# TheSiS.net
KiCad netlist of a schematic drawn in EAGLE
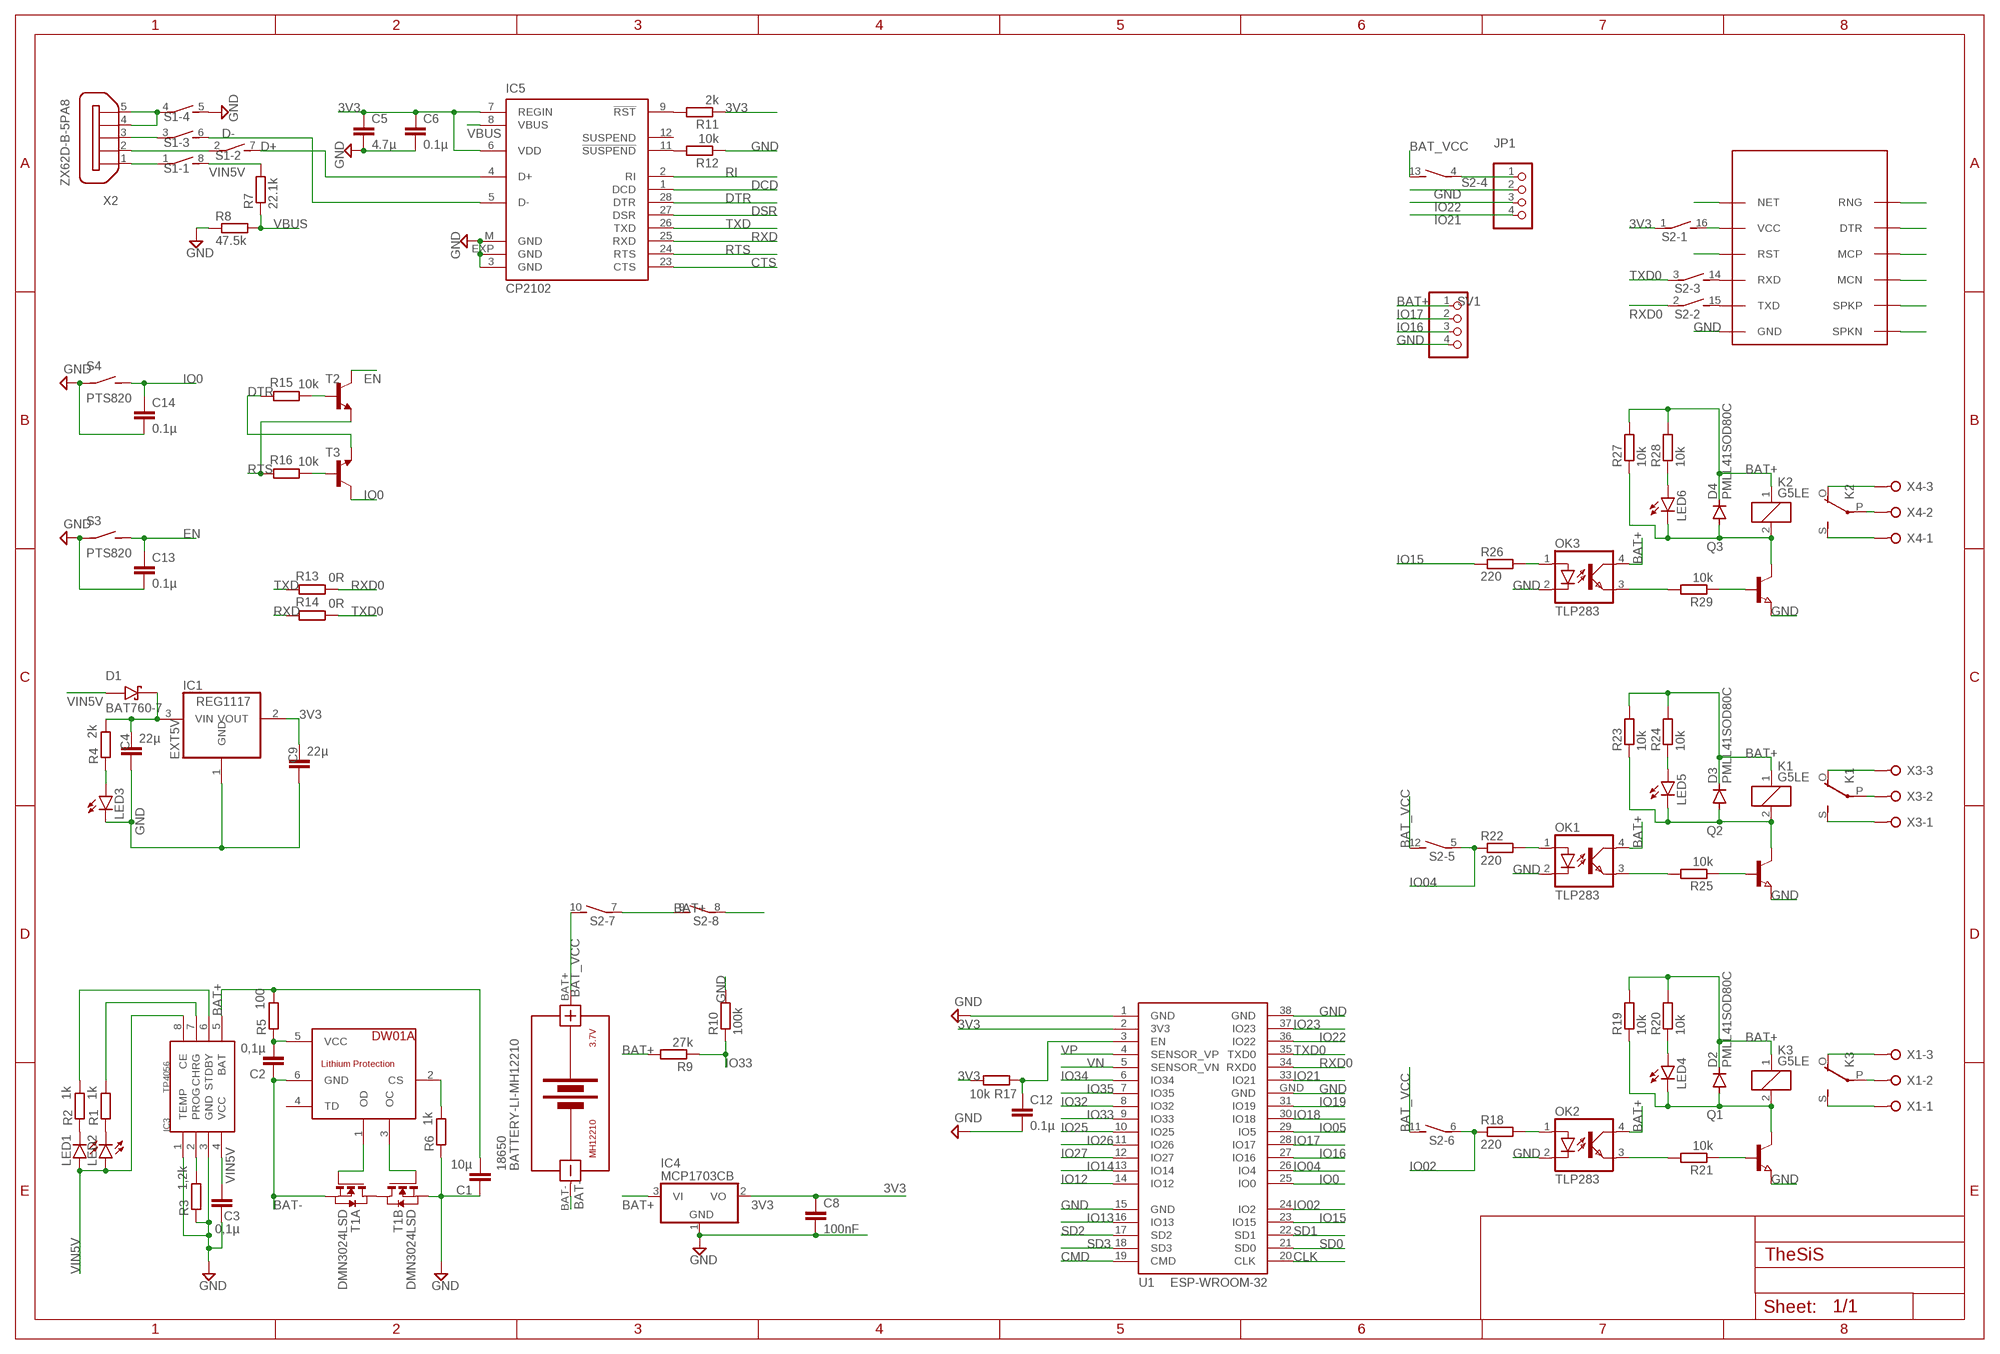
[diagram p0: schematic, sheet 1]

(export (version "E")
  (design (tool "Eeschema 10.0.6"))
  (components
    (comp (ref "18650")
      (value "BATTERY-LI-MH12210")
      (footprint "eagle-import:BATTERY-LI-MH12210")
      (libsource (lib "eagle-import") (part "BATTERY-LI-MH12210"))
    )
    (comp (ref "C1")
      (value "10µ")
      (footprint "eagle-import:C0603")
      (libsource (lib "eagle-import") (part "C-EUC0603"))
    )
    (comp (ref "C2")
      (value "0,1µ")
      (footprint "eagle-import:C0805")
      (libsource (lib "eagle-import") (part "C-EUC0805"))
    )
    (comp (ref "C3")
      (value "0,1µ")
      (footprint "eagle-import:C0805K")
      (libsource (lib "eagle-import") (part "C-EUC0805K"))
    )
    (comp (ref "C4")
      (value "22µ")
      (footprint "eagle-import:C0805")
      (libsource (lib "eagle-import") (part "C-EUC0805"))
    )
    (comp (ref "C5")
      (value "4.7µ")
      (footprint "eagle-import:C0805")
      (libsource (lib "eagle-import") (part "C-EUC0805"))
    )
    (comp (ref "C6")
      (value "0.1µ")
      (footprint "eagle-import:C0805")
      (libsource (lib "eagle-import") (part "C-EUC0805"))
    )
    (comp (ref "C8")
      (value "100nF")
      (footprint "eagle-import:C0805")
      (libsource (lib "eagle-import") (part "C-EUC0805"))
    )
    (comp (ref "C9")
      (value "22µ")
      (footprint "eagle-import:C0805")
      (libsource (lib "eagle-import") (part "C-EUC0805"))
    )
    (comp (ref "C12")
      (value "0.1µ")
      (footprint "eagle-import:C0805")
      (libsource (lib "eagle-import") (part "C-EUC0805"))
    )
    (comp (ref "C13")
      (value "0.1µ")
      (footprint "eagle-import:C0805")
      (libsource (lib "eagle-import") (part "C-EUC0805"))
    )
    (comp (ref "C14")
      (value "0.1µ")
      (footprint "eagle-import:C0805")
      (libsource (lib "eagle-import") (part "C-EUC0805"))
    )
    (comp (ref "D1")
      (value "BAT760-7")
      (footprint "eagle-import:SOD2513X120N")
      (fields (field (name "MF") "Diodes Inc."))
      (libsource (lib "eagle-import") (part "BAT760-7"))
    )
    (comp (ref "D2")
      (value "PMLL41SOD80C")
      (footprint "eagle-import:SOD80C")
      (libsource (lib "eagle-import") (part "PMLL41SOD80C"))
    )
    (comp (ref "D3")
      (value "PMLL41SOD80C")
      (footprint "eagle-import:SOD80C")
      (libsource (lib "eagle-import") (part "PMLL41SOD80C"))
    )
    (comp (ref "D4")
      (value "PMLL41SOD80C")
      (footprint "eagle-import:SOD80C")
      (libsource (lib "eagle-import") (part "PMLL41SOD80C"))
    )
    (comp (ref "IC1")
      (value "REG1117")
      (footprint "eagle-import:SOT223A")
      (libsource (lib "eagle-import") (part "REG1117"))
    )
    (comp (ref "IC3")
      (value "TP4056")
      (footprint "eagle-import:SOP-8")
      (libsource (lib "eagle-import") (part "TP4056"))
    )
    (comp (ref "IC4")
      (value "MCP1703CB")
      (footprint "eagle-import:SOT23")
      (libsource (lib "eagle-import") (part "MCP1703CB"))
    )
    (comp (ref "IC5")
      (value "CP2102")
      (footprint "eagle-import:QFN28")
      (fields (field (name "MF") "FARNELL") (field (name "MPN") "CP2102-GM"))
      (libsource (lib "eagle-import") (part "CP2102"))
    )
    (comp (ref "JP1")
      (value "PINHD-1X4")
      (footprint "eagle-import:1X04")
      (libsource (lib "eagle-import") (part "PINHD-1X4"))
    )
    (comp (ref "K1")
      (value "G5LE")
      (footprint "eagle-import:G5LE")
      (libsource (lib "eagle-import") (part "G5LE"))
    )
    (comp (ref "K2")
      (value "G5LE")
      (footprint "eagle-import:G5LE")
      (libsource (lib "eagle-import") (part "G5LE"))
    )
    (comp (ref "K3")
      (value "G5LE")
      (footprint "eagle-import:G5LE")
      (libsource (lib "eagle-import") (part "G5LE"))
    )
    (comp (ref "LED1")
      (value "LEDCHIP-LED0805")
      (footprint "eagle-import:CHIP-LED0805")
      (libsource (lib "eagle-import") (part "LEDCHIP-LED0805"))
    )
    (comp (ref "LED2")
      (value "LEDCHIP-LED0805")
      (footprint "eagle-import:CHIP-LED0805")
      (libsource (lib "eagle-import") (part "LEDCHIP-LED0805"))
    )
    (comp (ref "LED3")
      (value "LEDCHIP-LED0805")
      (footprint "eagle-import:CHIP-LED0805")
      (libsource (lib "eagle-import") (part "LEDCHIP-LED0805"))
    )
    (comp (ref "LED4")
      (value "LEDCHIP-LED0805")
      (footprint "eagle-import:CHIP-LED0805")
      (libsource (lib "eagle-import") (part "LEDCHIP-LED0805"))
    )
    (comp (ref "LED5")
      (value "LEDCHIP-LED0805")
      (footprint "eagle-import:CHIP-LED0805")
      (libsource (lib "eagle-import") (part "LEDCHIP-LED0805"))
    )
    (comp (ref "LED6")
      (value "LEDCHIP-LED0805")
      (footprint "eagle-import:CHIP-LED0805")
      (libsource (lib "eagle-import") (part "LEDCHIP-LED0805"))
    )
    (comp (ref "OK1")
      (value "TLP283")
      (footprint "eagle-import:SOT23-4")
      (libsource (lib "eagle-import") (part "TLP283"))
    )
    (comp (ref "OK2")
      (value "TLP283")
      (footprint "eagle-import:SOT23-4")
      (libsource (lib "eagle-import") (part "TLP283"))
    )
    (comp (ref "OK3")
      (value "TLP283")
      (footprint "eagle-import:SOT23-4")
      (libsource (lib "eagle-import") (part "TLP283"))
    )
    (comp (ref "Q1")
      (value "NPN-TRANSISTOR_SOT23")
      (footprint "eagle-import:SOT23")
      (libsource (lib "eagle-import") (part "NPN-TRANSISTOR_SOT23"))
    )
    (comp (ref "Q2")
      (value "NPN-TRANSISTOR_SOT23")
      (footprint "eagle-import:SOT23")
      (libsource (lib "eagle-import") (part "NPN-TRANSISTOR_SOT23"))
    )
    (comp (ref "Q3")
      (value "NPN-TRANSISTOR_SOT23")
      (footprint "eagle-import:SOT23")
      (libsource (lib "eagle-import") (part "NPN-TRANSISTOR_SOT23"))
    )
    (comp (ref "R1")
      (value "1k")
      (footprint "eagle-import:R0603")
      (libsource (lib "eagle-import") (part "R-EU_R0603"))
    )
    (comp (ref "R2")
      (value "1k")
      (footprint "eagle-import:R0603")
      (libsource (lib "eagle-import") (part "R-EU_R0603"))
    )
    (comp (ref "R3")
      (value "1,2k")
      (footprint "eagle-import:R0603")
      (libsource (lib "eagle-import") (part "R-EU_R0603"))
    )
    (comp (ref "R4")
      (value "2k")
      (footprint "eagle-import:R0805")
      (libsource (lib "eagle-import") (part "R-EU_R0805"))
    )
    (comp (ref "R5")
      (value "100")
      (footprint "eagle-import:R0603")
      (libsource (lib "eagle-import") (part "R-EU_R0603"))
    )
    (comp (ref "R6")
      (value "1k")
      (footprint "eagle-import:R0603")
      (libsource (lib "eagle-import") (part "R-EU_R0603"))
    )
    (comp (ref "R7")
      (value "22.1k")
      (footprint "eagle-import:R0805")
      (libsource (lib "eagle-import") (part "R-EU_R0805"))
    )
    (comp (ref "R8")
      (value "47.5k")
      (footprint "eagle-import:R0805")
      (libsource (lib "eagle-import") (part "R-EU_R0805"))
    )
    (comp (ref "R9")
      (value "27k")
      (footprint "eagle-import:R0805")
      (libsource (lib "eagle-import") (part "R-EU_R0805"))
    )
    (comp (ref "R10")
      (value "100k")
      (footprint "eagle-import:R0805")
      (libsource (lib "eagle-import") (part "R-EU_R0805"))
    )
    (comp (ref "R11")
      (value "2k")
      (footprint "eagle-import:R0805")
      (libsource (lib "eagle-import") (part "R-EU_R0805"))
    )
    (comp (ref "R12")
      (value "10k")
      (footprint "eagle-import:R0805")
      (libsource (lib "eagle-import") (part "R-EU_R0805"))
    )
    (comp (ref "R13")
      (value "0R")
      (footprint "eagle-import:R0805")
      (libsource (lib "eagle-import") (part "R-EU_R0805"))
    )
    (comp (ref "R14")
      (value "0R")
      (footprint "eagle-import:R0805")
      (libsource (lib "eagle-import") (part "R-EU_R0805"))
    )
    (comp (ref "R15")
      (value "10k")
      (footprint "eagle-import:R0805")
      (libsource (lib "eagle-import") (part "R-EU_R0805"))
    )
    (comp (ref "R16")
      (value "10k")
      (footprint "eagle-import:R0805")
      (libsource (lib "eagle-import") (part "R-EU_R0805"))
    )
    (comp (ref "R17")
      (value "10k")
      (footprint "eagle-import:R0805")
      (libsource (lib "eagle-import") (part "R-EU_R0805"))
    )
    (comp (ref "R18")
      (value "220")
      (footprint "eagle-import:R0805")
      (libsource (lib "eagle-import") (part "R-EU_R0805"))
    )
    (comp (ref "R19")
      (value "10k")
      (footprint "eagle-import:R0805")
      (libsource (lib "eagle-import") (part "R-EU_R0805"))
    )
    (comp (ref "R20")
      (value "10k")
      (footprint "eagle-import:R0805")
      (libsource (lib "eagle-import") (part "R-EU_R0805"))
    )
    (comp (ref "R21")
      (value "10k")
      (footprint "eagle-import:R0805")
      (libsource (lib "eagle-import") (part "R-EU_R0805"))
    )
    (comp (ref "R22")
      (value "220")
      (footprint "eagle-import:R0805")
      (libsource (lib "eagle-import") (part "R-EU_R0805"))
    )
    (comp (ref "R23")
      (value "10k")
      (footprint "eagle-import:R0805")
      (libsource (lib "eagle-import") (part "R-EU_R0805"))
    )
    (comp (ref "R24")
      (value "10k")
      (footprint "eagle-import:R0805")
      (libsource (lib "eagle-import") (part "R-EU_R0805"))
    )
    (comp (ref "R25")
      (value "10k")
      (footprint "eagle-import:R0805")
      (libsource (lib "eagle-import") (part "R-EU_R0805"))
    )
    (comp (ref "R26")
      (value "220")
      (footprint "eagle-import:R0805")
      (libsource (lib "eagle-import") (part "R-EU_R0805"))
    )
    (comp (ref "R27")
      (value "10k")
      (footprint "eagle-import:R0805")
      (libsource (lib "eagle-import") (part "R-EU_R0805"))
    )
    (comp (ref "R28")
      (value "10k")
      (footprint "eagle-import:R0805")
      (libsource (lib "eagle-import") (part "R-EU_R0805"))
    )
    (comp (ref "R29")
      (value "10k")
      (footprint "eagle-import:R0805")
      (libsource (lib "eagle-import") (part "R-EU_R0805"))
    )
    (comp (ref "S1")
      (value "DIP04S")
      (footprint "eagle-import:DIP04S")
      (libsource (lib "eagle-import") (part "DIP04S"))
    )
    (comp (ref "S2")
      (value "DIP08S")
      (footprint "eagle-import:DIP08S")
      (libsource (lib "eagle-import") (part "DIP08S"))
    )
    (comp (ref "S3")
      (value "PTS820")
      (footprint "eagle-import:PTS820")
      (libsource (lib "eagle-import") (part "PTS820"))
    )
    (comp (ref "S4")
      (value "PTS820")
      (footprint "eagle-import:PTS820")
      (libsource (lib "eagle-import") (part "PTS820"))
    )
    (comp (ref "SV1")
      (value "PINHD-1X4")
      (footprint "eagle-import:1X04")
      (libsource (lib "eagle-import") (part "PINHD-1X4"))
    )
    (comp (ref "T1")
      (value "DMN3024LSD")
      (footprint "eagle-import:TSSOP-8")
      (libsource (lib "eagle-import") (part "DMN3024LSD"))
    )
    (comp (ref "T2")
      (value "-NPN-SOT23-EBC")
      (footprint "eagle-import:SOT23-EBC")
      (fields (field (name "SPICEPREFIX") "J"))
      (libsource (lib "eagle-import") (part "-NPN-SOT23-EBC"))
    )
    (comp (ref "T3")
      (value "-NPN-SOT23-EBC")
      (footprint "eagle-import:SOT23-EBC")
      (fields (field (name "SPICEPREFIX") "J"))
      (libsource (lib "eagle-import") (part "-NPN-SOT23-EBC"))
    )
    (comp (ref "U$1")
      (value "DW01A")
      (footprint "eagle-import:SOT23-6")
      (libsource (lib "eagle-import") (part "DW01A"))
    )
    (comp (ref "U$4")
      (value "SIM800L")
      (footprint "eagle-import:SIM-CORE")
      (libsource (lib "eagle-import") (part "SIM800L"))
    )
    (comp (ref "U1")
      (value "ESP-WROOM-32")
      (footprint "eagle-import:ESP-WROOM-32")
      (libsource (lib "eagle-import") (part "ESP-WROOM-32"))
    )
    (comp (ref "X1")
      (value "W237-03P")
      (footprint "eagle-import:W237-3")
      (libsource (lib "eagle-import") (part "W237-03P"))
    )
    (comp (ref "X2")
      (value "ZX62D-B-5PA8")
      (footprint "eagle-import:ZX62D-B-5PA8")
      (fields (field (name "MF") "Hirose"))
      (libsource (lib "eagle-import") (part "ZX62D-B-5PA8"))
    )
    (comp (ref "X3")
      (value "W237-03P")
      (footprint "eagle-import:W237-3")
      (libsource (lib "eagle-import") (part "W237-03P"))
    )
    (comp (ref "X4")
      (value "W237-03P")
      (footprint "eagle-import:W237-3")
      (libsource (lib "eagle-import") (part "W237-03P"))
    )
  )
  (nets
    (net (code "1") (name "/3V3") (class "Default")
      (node (ref "C5") (pin "1") (pinfunction "1_1") (pintype "passive"))
      (node (ref "C6") (pin "1") (pinfunction "1_1") (pintype "passive"))
      (node (ref "C8") (pin "1") (pinfunction "1_1") (pintype "passive"))
      (node (ref "C9") (pin "1") (pinfunction "1_1") (pintype "passive"))
      (node (ref "IC1") (pin "2") (pinfunction "VOUT_2") (pintype "output"))
      (node (ref "IC4") (pin "2") (pinfunction "VO_2") (pintype "passive"))
      (node (ref "IC5") (pin "6") (pinfunction "VDD_6") (pintype "power_in"))
      (node (ref "IC5") (pin "7") (pinfunction "REGIN_7") (pintype "passive"))
      (node (ref "R11") (pin "1") (pinfunction "1_1") (pintype "passive"))
      (node (ref "R17") (pin "2") (pinfunction "2_2") (pintype "passive"))
      (node (ref "S2") (pin "1") (pinfunction "1_1") (pintype "passive"))
      (node (ref "U1") (pin "2") (pinfunction "3V3_2") (pintype "power_in"))
    )
    (net (code "2") (name "/BAT+") (class "Default")
      (node (ref "C1") (pin "2") (pinfunction "2_2") (pintype "passive"))
      (node (ref "D2") (pin "C") (pinfunction "C_C") (pintype "passive"))
      (node (ref "D3") (pin "C") (pinfunction "C_C") (pintype "passive"))
      (node (ref "D4") (pin "C") (pinfunction "C_C") (pintype "passive"))
      (node (ref "IC3") (pin "5") (pinfunction "BAT_5") (pintype "bidirectional"))
      (node (ref "IC4") (pin "3") (pinfunction "VI_3") (pintype "input"))
      (node (ref "K1") (pin "1") (pinfunction "1_1") (pintype "passive"))
      (node (ref "K2") (pin "1") (pinfunction "1_1") (pintype "passive"))
      (node (ref "K3") (pin "1") (pinfunction "1_1") (pintype "passive"))
      (node (ref "OK1") (pin "4") (pinfunction "COL_4") (pintype "passive"))
      (node (ref "OK2") (pin "4") (pinfunction "COL_4") (pintype "passive"))
      (node (ref "OK3") (pin "4") (pinfunction "COL_4") (pintype "passive"))
      (node (ref "R19") (pin "2") (pinfunction "2_2") (pintype "passive"))
      (node (ref "R20") (pin "2") (pinfunction "2_2") (pintype "passive"))
      (node (ref "R23") (pin "2") (pinfunction "2_2") (pintype "passive"))
      (node (ref "R24") (pin "2") (pinfunction "2_2") (pintype "passive"))
      (node (ref "R27") (pin "2") (pinfunction "2_2") (pintype "passive"))
      (node (ref "R28") (pin "2") (pinfunction "2_2") (pintype "passive"))
      (node (ref "R5") (pin "2") (pinfunction "2_2") (pintype "passive"))
      (node (ref "R9") (pin "2") (pinfunction "2_2") (pintype "passive"))
      (node (ref "S2") (pin "8") (pinfunction "1_8") (pintype "passive"))
      (node (ref "SV1") (pin "1") (pinfunction "1_1") (pintype "passive"))
    )
    (net (code "3") (name "/BAT-") (class "Default")
      (node (ref "18650") (pin "BAT-") (pinfunction "BAT-_BAT-") (pintype "power_in"))
      (node (ref "C2") (pin "1") (pinfunction "1_1") (pintype "passive"))
      (node (ref "T1") (pin "2") (pinfunction "S_2") (pintype "passive"))
      (node (ref "T1") (pin "3") (pinfunction "S_3") (pintype "passive"))
      (node (ref "U$1") (pin "6") (pinfunction "GND_6") (pintype "bidirectional"))
    )
    (net (code "4") (name "/BAT_VCC") (class "Default")
      (node (ref "18650") (pin "BAT+") (pinfunction "BAT+_BAT+") (pintype "power_in"))
      (node (ref "S2") (pin "10") (pinfunction "2_10") (pintype "passive"))
      (node (ref "S2") (pin "11") (pinfunction "2_11") (pintype "passive"))
      (node (ref "S2") (pin "12") (pinfunction "2_12") (pintype "passive"))
      (node (ref "S2") (pin "13") (pinfunction "2_13") (pintype "passive"))
    )
    (net (code "5") (name "/CLK") (class "Default")
      (node (ref "U1") (pin "20") (pinfunction "CLK_20") (pintype "bidirectional"))
    )
    (net (code "6") (name "/CMD") (class "Default")
      (node (ref "U1") (pin "19") (pinfunction "CMD_19") (pintype "bidirectional"))
    )
    (net (code "7") (name "/CTS") (class "Default")
      (node (ref "IC5") (pin "23") (pinfunction "CTS_23") (pintype "input"))
    )
    (net (code "8") (name "/D+") (class "Default")
      (node (ref "IC5") (pin "4") (pinfunction "D+_4") (pintype "bidirectional"))
      (node (ref "S1") (pin "7") (pinfunction "2_7") (pintype "passive"))
    )
    (net (code "9") (name "/D-") (class "Default")
      (node (ref "IC5") (pin "5") (pinfunction "D-_5") (pintype "bidirectional"))
      (node (ref "S1") (pin "6") (pinfunction "2_6") (pintype "passive"))
    )
    (net (code "10") (name "/DCD") (class "Default")
      (node (ref "IC5") (pin "1") (pinfunction "DCD_1") (pintype "input"))
    )
    (net (code "11") (name "/DSR") (class "Default")
      (node (ref "IC5") (pin "27") (pinfunction "DSR_27") (pintype "input"))
    )
    (net (code "12") (name "/DTR") (class "Default")
      (node (ref "IC5") (pin "28") (pinfunction "DTR_28") (pintype "output"))
      (node (ref "R15") (pin "2") (pinfunction "2_2") (pintype "passive"))
      (node (ref "T3") (pin "E") (pinfunction "E_E") (pintype "passive"))
    )
    (net (code "13") (name "/EN") (class "Default")
      (node (ref "C13") (pin "1") (pinfunction "1_1") (pintype "passive"))
      (node (ref "S3") (pin "2") (pinfunction "S_2") (pintype "passive"))
      (node (ref "T2") (pin "C") (pinfunction "C_C") (pintype "passive"))
    )
    (net (code "14") (name "/EXT5V") (class "Default")
      (node (ref "C4") (pin "1") (pinfunction "1_1") (pintype "passive"))
      (node (ref "D1") (pin "C") (pinfunction "K_C") (pintype "passive"))
      (node (ref "IC1") (pin "3") (pinfunction "VIN_3") (pintype "input"))
      (node (ref "R4") (pin "2") (pinfunction "2_2") (pintype "passive"))
    )
    (net (code "15") (name "/IO0") (class "Default")
      (node (ref "C14") (pin "1") (pinfunction "1_1") (pintype "passive"))
      (node (ref "S4") (pin "2") (pinfunction "S_2") (pintype "passive"))
      (node (ref "T3") (pin "C") (pinfunction "C_C") (pintype "passive"))
      (node (ref "U1") (pin "25") (pinfunction "IO0_25") (pintype "bidirectional"))
    )
    (net (code "16") (name "/IO02") (class "Default")
      (node (ref "R18") (pin "1") (pinfunction "1_1") (pintype "passive"))
      (node (ref "S2") (pin "6") (pinfunction "1_6") (pintype "passive"))
      (node (ref "U1") (pin "24") (pinfunction "IO2_24") (pintype "bidirectional"))
    )
    (net (code "17") (name "/IO04") (class "Default")
      (node (ref "R22") (pin "1") (pinfunction "1_1") (pintype "passive"))
      (node (ref "S2") (pin "5") (pinfunction "1_5") (pintype "passive"))
      (node (ref "U1") (pin "26") (pinfunction "IO4_26") (pintype "bidirectional"))
    )
    (net (code "18") (name "/IO05") (class "Default")
      (node (ref "U1") (pin "29") (pinfunction "IO5_29") (pintype "bidirectional"))
    )
    (net (code "19") (name "/IO12") (class "Default")
      (node (ref "U1") (pin "14") (pinfunction "IO12_14") (pintype "bidirectional"))
    )
    (net (code "20") (name "/IO13") (class "Default")
      (node (ref "U1") (pin "16") (pinfunction "IO13_16") (pintype "bidirectional"))
    )
    (net (code "21") (name "/IO14") (class "Default")
      (node (ref "U1") (pin "13") (pinfunction "IO14_13") (pintype "bidirectional"))
    )
    (net (code "22") (name "/IO15") (class "Default")
      (node (ref "R26") (pin "1") (pinfunction "1_1") (pintype "passive"))
      (node (ref "U1") (pin "23") (pinfunction "IO15_23") (pintype "bidirectional"))
    )
    (net (code "23") (name "/IO16") (class "Default")
      (node (ref "SV1") (pin "3") (pinfunction "3_3") (pintype "passive"))
      (node (ref "U1") (pin "27") (pinfunction "IO16_27") (pintype "bidirectional"))
    )
    (net (code "24") (name "/IO17") (class "Default")
      (node (ref "SV1") (pin "2") (pinfunction "2_2") (pintype "passive"))
      (node (ref "U1") (pin "28") (pinfunction "IO17_28") (pintype "bidirectional"))
    )
    (net (code "25") (name "/IO18") (class "Default")
      (node (ref "U1") (pin "30") (pinfunction "IO18_30") (pintype "bidirectional"))
    )
    (net (code "26") (name "/IO19") (class "Default")
      (node (ref "U1") (pin "31") (pinfunction "IO19_31") (pintype "bidirectional"))
    )
    (net (code "27") (name "/IO21") (class "Default")
      (node (ref "JP1") (pin "4") (pinfunction "4_4") (pintype "passive"))
      (node (ref "U1") (pin "33") (pinfunction "IO21_33") (pintype "bidirectional"))
    )
    (net (code "28") (name "/IO22") (class "Default")
      (node (ref "JP1") (pin "3") (pinfunction "3_3") (pintype "passive"))
      (node (ref "U1") (pin "36") (pinfunction "IO22_36") (pintype "bidirectional"))
    )
    (net (code "29") (name "/IO23") (class "Default")
      (node (ref "U1") (pin "37") (pinfunction "IO23_37") (pintype "bidirectional"))
    )
    (net (code "30") (name "/IO25") (class "Default")
      (node (ref "U1") (pin "10") (pinfunction "IO25_10") (pintype "bidirectional"))
    )
    (net (code "31") (name "/IO26") (class "Default")
      (node (ref "U1") (pin "11") (pinfunction "IO26_11") (pintype "bidirectional"))
    )
    (net (code "32") (name "/IO27") (class "Default")
      (node (ref "U1") (pin "12") (pinfunction "IO27_12") (pintype "bidirectional"))
    )
    (net (code "33") (name "/IO32") (class "Default")
      (node (ref "U1") (pin "8") (pinfunction "IO32_8") (pintype "bidirectional"))
    )
    (net (code "34") (name "/IO33") (class "Default")
      (node (ref "R10") (pin "1") (pinfunction "1_1") (pintype "passive"))
      (node (ref "R9") (pin "1") (pinfunction "1_1") (pintype "passive"))
      (node (ref "U1") (pin "9") (pinfunction "IO33_9") (pintype "bidirectional"))
    )
    (net (code "35") (name "/IO34") (class "Default")
      (node (ref "U1") (pin "6") (pinfunction "IO34_6") (pintype "bidirectional"))
    )
    (net (code "36") (name "/IO35") (class "Default")
      (node (ref "U1") (pin "7") (pinfunction "IO35_7") (pintype "bidirectional"))
    )
    (net (code "37") (name "/RI") (class "Default")
      (node (ref "IC5") (pin "2") (pinfunction "RI_2") (pintype "input"))
    )
    (net (code "38") (name "/RTS") (class "Default")
      (node (ref "IC5") (pin "24") (pinfunction "RTS_24") (pintype "output"))
      (node (ref "R16") (pin "2") (pinfunction "2_2") (pintype "passive"))
      (node (ref "T2") (pin "E") (pinfunction "E_E") (pintype "passive"))
    )
    (net (code "39") (name "/RXD") (class "Default")
      (node (ref "IC5") (pin "25") (pinfunction "RXD_25") (pintype "input"))
      (node (ref "R14") (pin "2") (pinfunction "2_2") (pintype "passive"))
    )
    (net (code "40") (name "/RXD0") (class "Default")
      (node (ref "R13") (pin "1") (pinfunction "1_1") (pintype "passive"))
      (node (ref "S2") (pin "2") (pinfunction "1_2") (pintype "passive"))
      (node (ref "U1") (pin "34") (pinfunction "RXD0_34") (pintype "bidirectional"))
    )
    (net (code "41") (name "/SD0") (class "Default")
      (node (ref "U1") (pin "21") (pinfunction "SD0_21") (pintype "bidirectional"))
    )
    (net (code "42") (name "/SD1") (class "Default")
      (node (ref "U1") (pin "22") (pinfunction "SD1_22") (pintype "bidirectional"))
    )
    (net (code "43") (name "/SD2") (class "Default")
      (node (ref "U1") (pin "17") (pinfunction "SD2_17") (pintype "bidirectional"))
    )
    (net (code "44") (name "/SD3") (class "Default")
      (node (ref "U1") (pin "18") (pinfunction "SD3_18") (pintype "bidirectional"))
    )
    (net (code "45") (name "/TXD") (class "Default")
      (node (ref "IC5") (pin "26") (pinfunction "TXD_26") (pintype "output"))
      (node (ref "R13") (pin "2") (pinfunction "2_2") (pintype "passive"))
    )
    (net (code "46") (name "/TXD0") (class "Default")
      (node (ref "R14") (pin "1") (pinfunction "1_1") (pintype "passive"))
      (node (ref "S2") (pin "3") (pinfunction "1_3") (pintype "passive"))
      (node (ref "U1") (pin "35") (pinfunction "TXD0_35") (pintype "bidirectional"))
    )
    (net (code "47") (name "/VBUS") (class "Default")
      (node (ref "IC5") (pin "8") (pinfunction "VBUS_8") (pintype "input"))
      (node (ref "R7") (pin "1") (pinfunction "1_1") (pintype "passive"))
      (node (ref "R8") (pin "2") (pinfunction "2_2") (pintype "passive"))
    )
    (net (code "48") (name "/VIN5V") (class "Default")
      (node (ref "C3") (pin "2") (pinfunction "2_2") (pintype "passive"))
      (node (ref "D1") (pin "A") (pinfunction "A_A") (pintype "passive"))
      (node (ref "IC3") (pin "4") (pinfunction "VCC_4") (pintype "bidirectional"))
      (node (ref "IC3") (pin "8") (pinfunction "CE_8") (pintype "bidirectional"))
      (node (ref "LED1") (pin "A") (pinfunction "A_A") (pintype "passive"))
      (node (ref "LED2") (pin "A") (pinfunction "A_A") (pintype "passive"))
      (node (ref "R7") (pin "2") (pinfunction "2_2") (pintype "passive"))
      (node (ref "S1") (pin "8") (pinfunction "2_8") (pintype "passive"))
    )
    (net (code "49") (name "/VN") (class "Default")
      (node (ref "U1") (pin "5") (pinfunction "SENSOR_VN_5") (pintype "bidirectional"))
    )
    (net (code "50") (name "/VP") (class "Default")
      (node (ref "U1") (pin "4") (pinfunction "SENSOR_VP_4") (pintype "bidirectional"))
    )
    (net (code "51") (name "GND") (class "Default")
      (node (ref "C1") (pin "1") (pinfunction "1_1") (pintype "passive"))
      (node (ref "C12") (pin "2") (pinfunction "2_2") (pintype "passive"))
      (node (ref "C13") (pin "2") (pinfunction "2_2") (pintype "passive"))
      (node (ref "C14") (pin "2") (pinfunction "2_2") (pintype "passive"))
      (node (ref "C3") (pin "1") (pinfunction "1_1") (pintype "passive"))
      (node (ref "C4") (pin "2") (pinfunction "2_2") (pintype "passive"))
      (node (ref "C5") (pin "2") (pinfunction "2_2") (pintype "passive"))
      (node (ref "C6") (pin "2") (pinfunction "2_2") (pintype "passive"))
      (node (ref "C8") (pin "2") (pinfunction "2_2") (pintype "passive"))
      (node (ref "C9") (pin "2") (pinfunction "2_2") (pintype "passive"))
      (node (ref "IC1") (pin "1") (pinfunction "GND_1") (pintype "power_in"))
      (node (ref "IC3") (pin "1") (pinfunction "TEMP_1") (pintype "bidirectional"))
      (node (ref "IC3") (pin "3") (pinfunction "GND_3") (pintype "bidirectional"))
      (node (ref "IC4") (pin "1") (pinfunction "GND_1") (pintype "passive"))
      (node (ref "IC5") (pin "3") (pinfunction "GND_3") (pintype "power_in"))
      (node (ref "IC5") (pin "EXP") (pinfunction "GND_EXP") (pintype "power_in"))
      (node (ref "IC5") (pin "M") (pinfunction "GND_M") (pintype "power_in"))
      (node (ref "JP1") (pin "2") (pinfunction "2_2") (pintype "passive"))
      (node (ref "LED3") (pin "C") (pinfunction "C_C") (pintype "passive"))
      (node (ref "OK1") (pin "2") (pinfunction "C_2") (pintype "passive"))
      (node (ref "OK2") (pin "2") (pinfunction "C_2") (pintype "passive"))
      (node (ref "OK3") (pin "2") (pinfunction "C_2") (pintype "passive"))
      (node (ref "Q1") (pin "2") (pinfunction "E_2") (pintype "passive"))
      (node (ref "Q2") (pin "2") (pinfunction "E_2") (pintype "passive"))
      (node (ref "Q3") (pin "2") (pinfunction "E_2") (pintype "passive"))
      (node (ref "R10") (pin "2") (pinfunction "2_2") (pintype "passive"))
      (node (ref "R12") (pin "1") (pinfunction "1_1") (pintype "passive"))
      (node (ref "R3") (pin "1") (pinfunction "1_1") (pintype "passive"))
      (node (ref "R6") (pin "1") (pinfunction "1_1") (pintype "passive"))
      (node (ref "R8") (pin "1") (pinfunction "1_1") (pintype "passive"))
      (node (ref "S1") (pin "5") (pinfunction "2_5") (pintype "passive"))
      (node (ref "S3") (pin "1") (pinfunction "P_1") (pintype "passive"))
      (node (ref "S4") (pin "1") (pinfunction "P_1") (pintype "passive"))
      (node (ref "SV1") (pin "4") (pinfunction "4_4") (pintype "passive"))
      (node (ref "T1") (pin "6") (pinfunction "S_6") (pintype "passive"))
      (node (ref "T1") (pin "7") (pinfunction "S_7") (pintype "passive"))
      (node (ref "U$4") (pin "GND") (pinfunction "GND_GND") (pintype "bidirectional"))
      (node (ref "U1") (pin "1") (pinfunction "GND_1") (pintype "power_in"))
      (node (ref "U1") (pin "15") (pinfunction "GND_15") (pintype "power_in"))
      (node (ref "U1") (pin "38") (pinfunction "GND_38") (pintype "power_in"))
      (node (ref "U1") (pin "GND") (pinfunction "GND_GND") (pintype "power_in"))
    )
    (net (code "52") (name "Net-(IC3-CHRG)") (class "Default")
      (node (ref "IC3") (pin "7") (pinfunction "CHRG_7") (pintype "bidirectional"))
      (node (ref "R1") (pin "2") (pinfunction "2_2") (pintype "passive"))
    )
    (net (code "53") (name "Net-(IC3-PROG)") (class "Default")
      (node (ref "IC3") (pin "2") (pinfunction "PROG_2") (pintype "bidirectional"))
      (node (ref "R3") (pin "2") (pinfunction "2_2") (pintype "passive"))
    )
    (net (code "54") (name "Net-(IC3-STDBY)") (class "Default")
      (node (ref "IC3") (pin "6") (pinfunction "STDBY_6") (pintype "bidirectional"))
      (node (ref "R2") (pin "2") (pinfunction "2_2") (pintype "passive"))
    )
    (net (code "55") (name "Net-(IC5-~{RST})") (class "Default")
      (node (ref "IC5") (pin "9") (pinfunction "~{RST}_9") (pintype "bidirectional"))
      (node (ref "R11") (pin "2") (pinfunction "2_2") (pintype "passive"))
    )
    (net (code "56") (name "Net-(IC5-~{SUSPEND})") (class "Default")
      (node (ref "IC5") (pin "11") (pinfunction "~{SUSPEND}_11") (pintype "output"))
      (node (ref "R12") (pin "2") (pinfunction "2_2") (pintype "passive"))
    )
    (net (code "57") (name "Net-(LED1-PadC)") (class "Default")
      (node (ref "LED1") (pin "C") (pinfunction "C_C") (pintype "passive"))
      (node (ref "R2") (pin "1") (pinfunction "1_1") (pintype "passive"))
    )
    (net (code "58") (name "Net-(LED2-PadC)") (class "Default")
      (node (ref "LED2") (pin "C") (pinfunction "C_C") (pintype "passive"))
      (node (ref "R1") (pin "1") (pinfunction "1_1") (pintype "passive"))
    )
    (net (code "59") (name "Net-(LED3-PadA)") (class "Default")
      (node (ref "LED3") (pin "A") (pinfunction "A_A") (pintype "passive"))
      (node (ref "R4") (pin "1") (pinfunction "1_1") (pintype "passive"))
    )
    (net (code "60") (name "Net-(LED4-PadA)") (class "Default")
      (node (ref "LED4") (pin "A") (pinfunction "A_A") (pintype "passive"))
      (node (ref "R20") (pin "1") (pinfunction "1_1") (pintype "passive"))
    )
    (net (code "61") (name "Net-(LED5-PadA)") (class "Default")
      (node (ref "LED5") (pin "A") (pinfunction "A_A") (pintype "passive"))
      (node (ref "R24") (pin "1") (pinfunction "1_1") (pintype "passive"))
    )
    (net (code "62") (name "Net-(LED6-PadA)") (class "Default")
      (node (ref "LED6") (pin "A") (pinfunction "A_A") (pintype "passive"))
      (node (ref "R28") (pin "1") (pinfunction "1_1") (pintype "passive"))
    )
    (net (code "63") (name "Net-(OK1-A)") (class "Default")
      (node (ref "OK1") (pin "1") (pinfunction "A_1") (pintype "passive"))
      (node (ref "R22") (pin "2") (pinfunction "2_2") (pintype "passive"))
    )
    (net (code "64") (name "Net-(OK1-EMIT)") (class "Default")
      (node (ref "OK1") (pin "3") (pinfunction "EMIT_3") (pintype "passive"))
      (node (ref "R25") (pin "2") (pinfunction "2_2") (pintype "passive"))
    )
    (net (code "65") (name "Net-(OK2-A)") (class "Default")
      (node (ref "OK2") (pin "1") (pinfunction "A_1") (pintype "passive"))
      (node (ref "R18") (pin "2") (pinfunction "2_2") (pintype "passive"))
    )
    (net (code "66") (name "Net-(OK2-EMIT)") (class "Default")
      (node (ref "OK2") (pin "3") (pinfunction "EMIT_3") (pintype "passive"))
      (node (ref "R21") (pin "2") (pinfunction "2_2") (pintype "passive"))
    )
    (net (code "67") (name "Net-(OK3-A)") (class "Default")
      (node (ref "OK3") (pin "1") (pinfunction "A_1") (pintype "passive"))
      (node (ref "R26") (pin "2") (pinfunction "2_2") (pintype "passive"))
    )
    (net (code "68") (name "Net-(OK3-EMIT)") (class "Default")
      (node (ref "OK3") (pin "3") (pinfunction "EMIT_3") (pintype "passive"))
      (node (ref "R29") (pin "2") (pinfunction "2_2") (pintype "passive"))
    )
    (net (code "69") (name "Net-(Q1-B)") (class "Default")
      (node (ref "Q1") (pin "1") (pinfunction "B_1") (pintype "passive"))
      (node (ref "R21") (pin "1") (pinfunction "1_1") (pintype "passive"))
    )
    (net (code "70") (name "Net-(Q1-C)") (class "Default")
      (node (ref "D2") (pin "A") (pinfunction "A_A") (pintype "passive"))
      (node (ref "K3") (pin "2") (pinfunction "2_2") (pintype "passive"))
      (node (ref "LED4") (pin "C") (pinfunction "C_C") (pintype "passive"))
      (node (ref "Q1") (pin "3") (pinfunction "C_3") (pintype "passive"))
      (node (ref "R19") (pin "1") (pinfunction "1_1") (pintype "passive"))
    )
    (net (code "71") (name "Net-(Q2-B)") (class "Default")
      (node (ref "Q2") (pin "1") (pinfunction "B_1") (pintype "passive"))
      (node (ref "R25") (pin "1") (pinfunction "1_1") (pintype "passive"))
    )
    (net (code "72") (name "Net-(Q2-C)") (class "Default")
      (node (ref "D3") (pin "A") (pinfunction "A_A") (pintype "passive"))
      (node (ref "K1") (pin "2") (pinfunction "2_2") (pintype "passive"))
      (node (ref "LED5") (pin "C") (pinfunction "C_C") (pintype "passive"))
      (node (ref "Q2") (pin "3") (pinfunction "C_3") (pintype "passive"))
      (node (ref "R23") (pin "1") (pinfunction "1_1") (pintype "passive"))
    )
    (net (code "73") (name "Net-(Q3-B)") (class "Default")
      (node (ref "Q3") (pin "1") (pinfunction "B_1") (pintype "passive"))
      (node (ref "R29") (pin "1") (pinfunction "1_1") (pintype "passive"))
    )
    (net (code "74") (name "Net-(Q3-C)") (class "Default")
      (node (ref "D4") (pin "A") (pinfunction "A_A") (pintype "passive"))
      (node (ref "K2") (pin "2") (pinfunction "2_2") (pintype "passive"))
      (node (ref "LED6") (pin "C") (pinfunction "C_C") (pintype "passive"))
      (node (ref "Q3") (pin "3") (pinfunction "C_3") (pintype "passive"))
      (node (ref "R27") (pin "1") (pinfunction "1_1") (pintype "passive"))
    )
    (net (code "75") (name "Net-(R15-Pad1)") (class "Default")
      (node (ref "R15") (pin "1") (pinfunction "1_1") (pintype "passive"))
      (node (ref "T2") (pin "B") (pinfunction "B_B") (pintype "passive"))
    )
    (net (code "76") (name "Net-(R16-Pad1)") (class "Default")
      (node (ref "R16") (pin "1") (pinfunction "1_1") (pintype "passive"))
      (node (ref "T3") (pin "B") (pinfunction "B_B") (pintype "passive"))
    )
    (net (code "77") (name "Net-(S1-Pad1)") (class "Default")
      (node (ref "S1") (pin "1") (pinfunction "1_1") (pintype "passive"))
      (node (ref "X2") (pin "1") (pinfunction "1_1") (pintype "passive"))
    )
    (net (code "78") (name "Net-(S1B-1)") (class "Default")
      (node (ref "S1") (pin "2") (pinfunction "1_2") (pintype "passive"))
      (node (ref "X2") (pin "2") (pinfunction "2_2") (pintype "passive"))
    )
    (net (code "79") (name "Net-(S1C-1)") (class "Default")
      (node (ref "S1") (pin "3") (pinfunction "1_3") (pintype "passive"))
      (node (ref "X2") (pin "3") (pinfunction "3_3") (pintype "passive"))
    )
    (net (code "80") (name "Net-(S1D-1)") (class "Default")
      (node (ref "S1") (pin "4") (pinfunction "1_4") (pintype "passive"))
      (node (ref "X2") (pin "4") (pinfunction "4_4") (pintype "passive"))
      (node (ref "X2") (pin "5") (pinfunction "5_5") (pintype "passive"))
    )
    (net (code "81") (name "Net-(S2A-2)") (class "Default")
      (node (ref "S2") (pin "16") (pinfunction "2_16") (pintype "passive"))
      (node (ref "U$4") (pin "VCC") (pinfunction "VCC_VCC") (pintype "bidirectional"))
    )
    (net (code "82") (name "Net-(S2B-2)") (class "Default")
      (node (ref "S2") (pin "15") (pinfunction "2_15") (pintype "passive"))
      (node (ref "U$4") (pin "TXD") (pinfunction "TXD_TXD") (pintype "bidirectional"))
    )
    (net (code "83") (name "Net-(S2C-2)") (class "Default")
      (node (ref "S2") (pin "14") (pinfunction "2_14") (pintype "passive"))
      (node (ref "U$4") (pin "RXD") (pinfunction "RXD_RXD") (pintype "bidirectional"))
    )
    (net (code "84") (name "Net-(S2D-1)") (class "Default")
      (node (ref "JP1") (pin "1") (pinfunction "1_1") (pintype "passive"))
      (node (ref "S2") (pin "4") (pinfunction "1_4") (pintype "passive"))
    )
    (net (code "85") (name "Net-(S2G-1)") (class "Default")
      (node (ref "S2") (pin "7") (pinfunction "1_7") (pintype "passive"))
      (node (ref "S2") (pin "9") (pinfunction "2_9") (pintype "passive"))
    )
    (net (code "86") (name "Net-(T1A-D)") (class "Default")
      (node (ref "T1") (pin "1") (pinfunction "D_1") (pintype "passive"))
      (node (ref "T1") (pin "8") (pinfunction "D_8") (pintype "passive"))
    )
    (net (code "87") (name "Net-(T1A-G)") (class "Default")
      (node (ref "T1") (pin "4") (pinfunction "G_4") (pintype "passive"))
      (node (ref "U$1") (pin "1") (pinfunction "OD_1") (pintype "bidirectional"))
    )
    (net (code "88") (name "Net-(T1B-G)") (class "Default")
      (node (ref "T1") (pin "5") (pinfunction "G_5") (pintype "passive"))
      (node (ref "U$1") (pin "3") (pinfunction "OC_3") (pintype "bidirectional"))
    )
    (net (code "89") (name "Net-(U$1-CS)") (class "Default")
      (node (ref "R6") (pin "2") (pinfunction "2_2") (pintype "passive"))
      (node (ref "U$1") (pin "2") (pinfunction "CS_2") (pintype "bidirectional"))
    )
    (net (code "90") (name "Net-(U$1-VCC)") (class "Default")
      (node (ref "C2") (pin "2") (pinfunction "2_2") (pintype "passive"))
      (node (ref "R5") (pin "1") (pinfunction "1_1") (pintype "passive"))
      (node (ref "U$1") (pin "5") (pinfunction "VCC_5") (pintype "bidirectional"))
    )
    (net (code "91") (name "Net-(U1-EN)") (class "Default")
      (node (ref "C12") (pin "1") (pinfunction "1_1") (pintype "passive"))
      (node (ref "R17") (pin "1") (pinfunction "1_1") (pintype "passive"))
      (node (ref "U1") (pin "3") (pinfunction "EN_3") (pintype "input"))
    )
    (net (code "92") (name "Net-(X1A-KL)") (class "Default")
      (node (ref "K3") (pin "S") (pinfunction "S_S") (pintype "passive"))
      (node (ref "X1") (pin "1") (pinfunction "KL_1") (pintype "passive"))
    )
    (net (code "93") (name "Net-(X1B-KL)") (class "Default")
      (node (ref "K3") (pin "P") (pinfunction "P_P") (pintype "passive"))
      (node (ref "X1") (pin "2") (pinfunction "KL_2") (pintype "passive"))
    )
    (net (code "94") (name "Net-(X1C-KL)") (class "Default")
      (node (ref "K3") (pin "O") (pinfunction "O_O") (pintype "passive"))
      (node (ref "X1") (pin "3") (pinfunction "KL_3") (pintype "passive"))
    )
    (net (code "95") (name "Net-(X3A-KL)") (class "Default")
      (node (ref "K1") (pin "S") (pinfunction "S_S") (pintype "passive"))
      (node (ref "X3") (pin "1") (pinfunction "KL_1") (pintype "passive"))
    )
    (net (code "96") (name "Net-(X3B-KL)") (class "Default")
      (node (ref "K1") (pin "P") (pinfunction "P_P") (pintype "passive"))
      (node (ref "X3") (pin "2") (pinfunction "KL_2") (pintype "passive"))
    )
    (net (code "97") (name "Net-(X3C-KL)") (class "Default")
      (node (ref "K1") (pin "O") (pinfunction "O_O") (pintype "passive"))
      (node (ref "X3") (pin "3") (pinfunction "KL_3") (pintype "passive"))
    )
    (net (code "98") (name "Net-(X4A-KL)") (class "Default")
      (node (ref "K2") (pin "S") (pinfunction "S_S") (pintype "passive"))
      (node (ref "X4") (pin "1") (pinfunction "KL_1") (pintype "passive"))
    )
    (net (code "99") (name "Net-(X4B-KL)") (class "Default")
      (node (ref "K2") (pin "P") (pinfunction "P_P") (pintype "passive"))
      (node (ref "X4") (pin "2") (pinfunction "KL_2") (pintype "passive"))
    )
    (net (code "100") (name "Net-(X4C-KL)") (class "Default")
      (node (ref "K2") (pin "O") (pinfunction "O_O") (pintype "passive"))
      (node (ref "X4") (pin "3") (pinfunction "KL_3") (pintype "passive"))
    )
    (net (code "101") (name "unconnected-(IC5-SUSPEND-Pad12)") (class "Default")
      (node (ref "IC5") (pin "12") (pinfunction "SUSPEND_12") (pintype "output"))
    )
    (net (code "102") (name "unconnected-(U$1-TD-Pad4)") (class "Default")
      (node (ref "U$1") (pin "4") (pinfunction "TD_4") (pintype "bidirectional"))
    )
    (net (code "103") (name "unconnected-(U$4-PadDTR)") (class "Default")
      (node (ref "U$4") (pin "DTR") (pinfunction "DTR_DTR") (pintype "bidirectional"))
    )
    (net (code "104") (name "unconnected-(U$4-PadMCN)") (class "Default")
      (node (ref "U$4") (pin "MCN") (pinfunction "MCN_MCN") (pintype "bidirectional"))
    )
    (net (code "105") (name "unconnected-(U$4-PadMCP)") (class "Default")
      (node (ref "U$4") (pin "MCP") (pinfunction "MCP_MCP") (pintype "bidirectional"))
    )
    (net (code "106") (name "unconnected-(U$4-PadNET)") (class "Default")
      (node (ref "U$4") (pin "NET") (pinfunction "NET_NET") (pintype "bidirectional"))
    )
    (net (code "107") (name "unconnected-(U$4-PadRNG)") (class "Default")
      (node (ref "U$4") (pin "RNG") (pinfunction "RNG_RNG") (pintype "bidirectional"))
    )
    (net (code "108") (name "unconnected-(U$4-PadRST)") (class "Default")
      (node (ref "U$4") (pin "RST") (pinfunction "RST_RST") (pintype "bidirectional"))
    )
    (net (code "109") (name "unconnected-(U$4-PadSPKN)") (class "Default")
      (node (ref "U$4") (pin "SPKN") (pinfunction "SPKN_SPKN") (pintype "bidirectional"))
    )
    (net (code "110") (name "unconnected-(U$4-PadSPKP)") (class "Default")
      (node (ref "U$4") (pin "SPKP") (pinfunction "SPKP_SPKP") (pintype "bidirectional"))
    )
  )
)
